# Power.net
KiCad netlist of a schematic drawn in Altium Designer
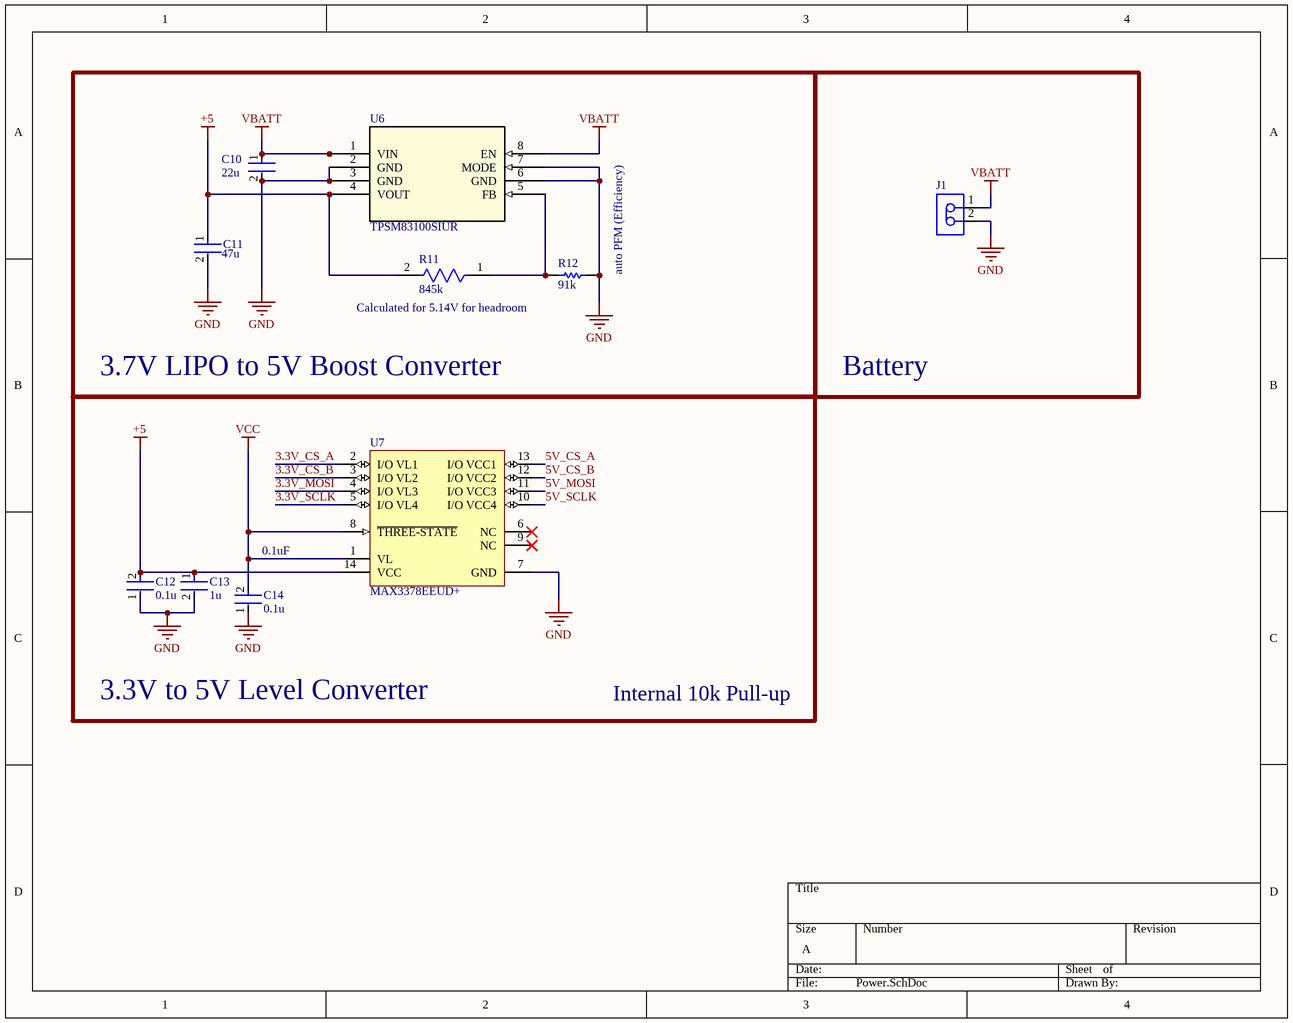
[diagram p0: Power.SchDoc]

(export (version "E")
  (design (tool "Eeschema 10.0.6"))
  (components
    (comp (ref "C10")
      (value "22u")
      (footprint "FP-GRM187-0_2-IPC_C")
      (description "Chip Multilayer Ceramic Capacitors for General Purpose, 0603, 22uF, X5R, 15%, 20%, 10V")
      (fields (field (name "TOLERANCE") "20%"))
      (libsource (lib "Altium Content Vault") (part "02cd4be3c70576c341d710602a673aa"))
    )
    (comp (ref "C11")
      (value "47u")
      (footprint "FP-GRM219-0_2-0_1-IPC_A")
      (description "Chip Multilayer Ceramic Capacitors for General Purpose, 0805, 47uF, X5R, 15%, 20%, 6.3V")
      (fields (field (name "TOLERANCE") "20%"))
      (libsource (lib "Altium Content Vault") (part "02cd4be3c70576c341d710602a673aa"))
    )
    (comp (ref "C12")
      (value "0.1u")
      (footprint "FP-GCJ188-0_2-IPC_C")
      (description "Cap Ceramic 0.1uF 50V X7R 10% Pad SMD 0603 Soft Termination +125°C Automotive T/R")
      (fields (field (name "TOLERANCE") "10%"))
      (libsource (lib "Altium Content Vault") (part "f23184f103b6ebe33a8c269c53dcba6"))
    )
    (comp (ref "C13")
      (value "1u")
      (footprint "FP-GCM188-0_1-IPC_B")
      (description "Ceramic Capacitor for Automotive 1uF  ±10% 16VDC X7R 0603 Paper T/R")
      (fields (field (name "VOLTAGE") "16V") (field (name "TOLERANCE") "10%"))
      (libsource (lib "Altium Content Vault") (part "02cd4be3c70576c341d710602a673aa"))
    )
    (comp (ref "C14")
      (value "0.1u")
      (footprint "FP-GCJ188-0_2-IPC_C")
      (description "Cap Ceramic 0.1uF 50V X7R 10% Pad SMD 0603 Soft Termination +125°C Automotive T/R")
      (fields (field (name "TOLERANCE") "10%"))
      (libsource (lib "Altium Content Vault") (part "f23184f103b6ebe33a8c269c53dcba6"))
    )
    (comp (ref "J1")
      (value "B2B-PH-K-S(LF)(SN)")
      (footprint "JST-B2B-PH-K-S_V")
      (fields (field (name "MANUFACTURER") "JST"))
      (libsource (lib "Altium Content Vault") (part "CN-2P-F-QF2"))
    )
    (comp (ref "R11")
      (value "845k")
      (footprint "FP-CR0603-IPC_B")
      (description "Thick Film Chip Resistors 0603 845kΩ 0.1W 1% 100ppm/°C")
      (fields (field (name "TOLERANCE") "1%"))
      (libsource (lib "Altium Content Vault") (part "1029c3af85768c4190bb7ad29bc67b5"))
    )
    (comp (ref "R12")
      (value "91k")
      (footprint "RESC1609X50X30NL10T20")
      (fields (field (name "PART NUMBER") "CRCW060391K0FKEA") (field (name "MANUFACTURER") "Vishay Dale"))
      (libsource (lib "Altium Content Vault") (part "RES"))
    )
    (comp (ref "U6")
      (value "TPSM83100SIUR")
      (footprint "MICROSIP8_SIU_TEX")
      (description "1.5-A high efficiency buck-boost module with integrated inductor")
      (libsource (lib "TPSM83100SIUR") (part "TPSM83100SIUR"))
    )
    (comp (ref "U7")
      (value "MAX3378EEUD+")
      (footprint "MAXM-U14+1_V")
      (libsource (lib "Altium Content Vault") (part "MAXM-MAX3378E-U14"))
    )
  )
  (nets
    (net (code "1") (name "+5") (class "Default")
      (node (ref "C11") (pin "1") (pinfunction "1_1") (pintype "passive"))
      (node (ref "C12") (pin "2") (pinfunction "2_2") (pintype "passive"))
      (node (ref "C13") (pin "1") (pinfunction "1_1") (pintype "passive"))
      (node (ref "R11") (pin "2") (pinfunction "2_2") (pintype "passive"))
      (node (ref "U6") (pin "4") (pinfunction "VOUT_4") (pintype "power_in"))
      (node (ref "U7") (pin "14") (pinfunction "VCC_14") (pintype "power_in"))
    )
    (net (code "2") (name "/3.3V_CS_A") (class "Default")
      (node (ref "U7") (pin "2") (pinfunction "I/O_VL1_2") (pintype "bidirectional"))
    )
    (net (code "3") (name "/3.3V_CS_B") (class "Default")
      (node (ref "U7") (pin "3") (pinfunction "I/O_VL2_3") (pintype "bidirectional"))
    )
    (net (code "4") (name "/3.3V_MOSI") (class "Default")
      (node (ref "U7") (pin "4") (pinfunction "I/O_VL3_4") (pintype "bidirectional"))
    )
    (net (code "5") (name "/3.3V_SCLK") (class "Default")
      (node (ref "U7") (pin "5") (pinfunction "I/O_VL4_5") (pintype "bidirectional"))
    )
    (net (code "6") (name "/5V_CS_A") (class "Default")
      (node (ref "U7") (pin "13") (pinfunction "I/O_VCC1_13") (pintype "bidirectional"))
    )
    (net (code "7") (name "/5V_CS_B") (class "Default")
      (node (ref "U7") (pin "12") (pinfunction "I/O_VCC2_12") (pintype "bidirectional"))
    )
    (net (code "8") (name "/5V_MOSI") (class "Default")
      (node (ref "U7") (pin "11") (pinfunction "I/O_VCC3_11") (pintype "bidirectional"))
    )
    (net (code "9") (name "/5V_SCLK") (class "Default")
      (node (ref "U7") (pin "10") (pinfunction "I/O_VCC4_10") (pintype "bidirectional"))
    )
    (net (code "10") (name "GND") (class "Default")
      (node (ref "C10") (pin "2") (pinfunction "2_2") (pintype "passive"))
      (node (ref "C11") (pin "2") (pinfunction "2_2") (pintype "passive"))
      (node (ref "C12") (pin "1") (pinfunction "1_1") (pintype "passive"))
      (node (ref "C13") (pin "2") (pinfunction "2_2") (pintype "passive"))
      (node (ref "C14") (pin "1") (pinfunction "1_1") (pintype "passive"))
      (node (ref "J1") (pin "2") (pinfunction "2_2") (pintype "passive"))
      (node (ref "R12") (pin "1") (pinfunction "1_1") (pintype "passive"))
      (node (ref "U6") (pin "2") (pinfunction "GND_2") (pintype "power_in"))
      (node (ref "U6") (pin "3") (pinfunction "GND_3") (pintype "power_in"))
      (node (ref "U6") (pin "6") (pinfunction "GND_6") (pintype "power_in"))
      (node (ref "U6") (pin "7") (pinfunction "MODE_7") (pintype "input"))
      (node (ref "U7") (pin "7") (pinfunction "GND_7") (pintype "power_in"))
    )
    (net (code "11") (name "Net-(U6-FB)") (class "Default")
      (node (ref "R11") (pin "1") (pinfunction "1_1") (pintype "passive"))
      (node (ref "R12") (pin "2") (pinfunction "2_2") (pintype "passive"))
      (node (ref "U6") (pin "5") (pinfunction "FB_5") (pintype "input"))
    )
    (net (code "12") (name "VBATT") (class "Default")
      (node (ref "C10") (pin "1") (pinfunction "1_1") (pintype "passive"))
      (node (ref "J1") (pin "1") (pinfunction "1_1") (pintype "passive"))
      (node (ref "U6") (pin "1") (pinfunction "VIN_1") (pintype "power_in"))
      (node (ref "U6") (pin "8") (pinfunction "EN_8") (pintype "input"))
    )
    (net (code "13") (name "VCC") (class "Default")
      (node (ref "C14") (pin "2") (pinfunction "2_2") (pintype "passive"))
      (node (ref "U7") (pin "1") (pinfunction "VL_1") (pintype "power_in"))
      (node (ref "U7") (pin "8") (pinfunction "~{THREE-STATE}_8") (pintype "input"))
    )
    (net (code "14") (name "unconnected-(U7-NC-Pad6)") (class "Default")
      (node (ref "U7") (pin "6") (pinfunction "NC_6") (pintype "passive+no_connect"))
    )
    (net (code "15") (name "unconnected-(U7-NC-Pad9)") (class "Default")
      (node (ref "U7") (pin "9") (pinfunction "NC_9") (pintype "passive+no_connect"))
    )
  )
)
